# motordriverboard.net
KiCad netlist of a schematic drawn in EAGLE
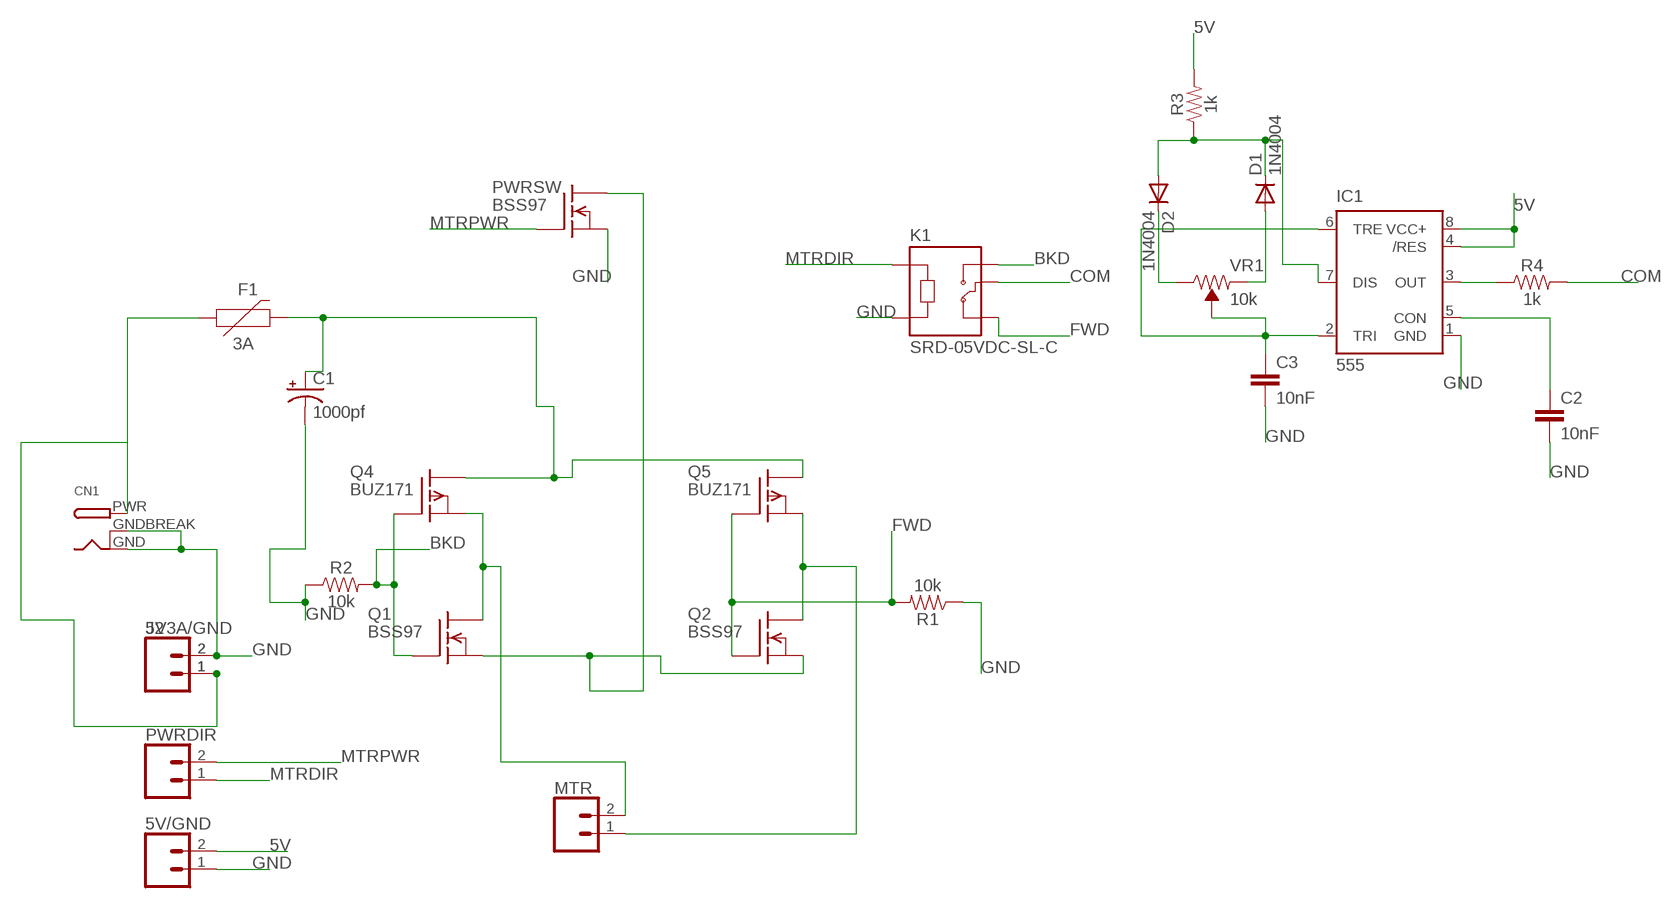
[diagram p0: schematic, sheet 1]

(export (version "E")
  (design (tool "Eeschema 10.0.6"))
  (components
    (comp (ref "5V/GND")
      (value "CONN_023.5MM")
      (footprint "eagle-import:SCREWTERMINAL-3.5MM-2")
      (libsource (lib "eagle-import") (part "CONN_023.5MM"))
    )
    (comp (ref "5V3A/GND")
      (value "CONN_023.5MM")
      (footprint "eagle-import:SCREWTERMINAL-3.5MM-2")
      (libsource (lib "eagle-import") (part "CONN_023.5MM"))
    )
    (comp (ref "C1")
      (value "1000pf")
      (footprint "eagle-import:E5-6")
      (libsource (lib "eagle-import") (part "CPOL-USE5-6"))
    )
    (comp (ref "C2")
      (value "10nF")
      (footprint "eagle-import:CAP-PTH-10MM")
      (libsource (lib "eagle-import") (part "10NF-PTH-10MM-10000V-1-%"))
    )
    (comp (ref "C3")
      (value "10nF")
      (footprint "eagle-import:CAP-PTH-10MM")
      (libsource (lib "eagle-import") (part "10NF-PTH-10MM-10000V-1-%"))
    )
    (comp (ref "CN1")
      (value "DCBARRELPTH")
      (footprint "eagle-import:DCJACK_2MM_PTH")
      (libsource (lib "eagle-import") (part "DCBARRELPTH"))
    )
    (comp (ref "D1")
      (value "1N4004")
      (footprint "eagle-import:DO41-10")
      (libsource (lib "eagle-import") (part "1N4004"))
    )
    (comp (ref "D2")
      (value "1N4004")
      (footprint "eagle-import:DO41-10")
      (libsource (lib "eagle-import") (part "1N4004"))
    )
    (comp (ref "F1")
      (value "3A")
      (footprint "eagle-import:PTH")
      (libsource (lib "eagle-import") (part "PPTC_PTH"))
    )
    (comp (ref "IC1")
      (value "555")
      (footprint "eagle-import:DIP08")
      (libsource (lib "eagle-import") (part "555P"))
    )
    (comp (ref "J2")
      (value "CONN_023.5MM")
      (footprint "eagle-import:SCREWTERMINAL-3.5MM-2")
      (libsource (lib "eagle-import") (part "CONN_023.5MM"))
    )
    (comp (ref "K1")
      (value "SRD-05VDC-SL-C")
      (footprint "eagle-import:RELAY_SRD-05VDC-SL-C")
      (fields (field (name "MF") "Songle Relay"))
      (libsource (lib "eagle-import") (part "SRD-05VDC-SL-C"))
    )
    (comp (ref "MTR")
      (value "CONN_023.5MM")
      (footprint "eagle-import:SCREWTERMINAL-3.5MM-2")
      (libsource (lib "eagle-import") (part "CONN_023.5MM"))
    )
    (comp (ref "PWRDIR")
      (value "CONN_023.5MM")
      (footprint "eagle-import:SCREWTERMINAL-3.5MM-2")
      (libsource (lib "eagle-import") (part "CONN_023.5MM"))
    )
    (comp (ref "PWRSW")
      (value "BSS97")
      (footprint "eagle-import:TO202")
      (libsource (lib "eagle-import") (part "BSS97"))
    )
    (comp (ref "Q1")
      (value "BSS97")
      (footprint "eagle-import:TO202")
      (libsource (lib "eagle-import") (part "BSS97"))
    )
    (comp (ref "Q2")
      (value "BSS97")
      (footprint "eagle-import:TO202")
      (libsource (lib "eagle-import") (part "BSS97"))
    )
    (comp (ref "Q4")
      (value "BUZ171")
      (footprint "eagle-import:TO220")
      (libsource (lib "eagle-import") (part "BUZ171"))
    )
    (comp (ref "Q5")
      (value "BUZ171")
      (footprint "eagle-import:TO220")
      (libsource (lib "eagle-import") (part "BUZ171"))
    )
    (comp (ref "R1")
      (value "10k")
      (footprint "eagle-import:AXIAL-0.3")
      (libsource (lib "eagle-import") (part "15KOHM-HORIZ-1/4W-5%"))
    )
    (comp (ref "R2")
      (value "10k")
      (footprint "eagle-import:AXIAL-0.3")
      (libsource (lib "eagle-import") (part "15KOHM-HORIZ-1/4W-5%"))
    )
    (comp (ref "R3")
      (value "1k")
      (footprint "eagle-import:AXIAL-0.3")
      (libsource (lib "eagle-import") (part "1KOHM-HORIZ-1/4W-1%"))
    )
    (comp (ref "R4")
      (value "1k")
      (footprint "eagle-import:AXIAL-0.3")
      (libsource (lib "eagle-import") (part "1KOHM-HORIZ-1/4W-1%"))
    )
    (comp (ref "VR1")
      (value "10k")
      (footprint "eagle-import:TRIMPOT-PTH-3386U")
      (libsource (lib "eagle-import") (part "TRIMPOT-PTH-10MM-KNOB-1/2W-10%"))
    )
  )
  (nets
    (net (code "1") (name "/5V") (class "Default")
      (node (ref "5V/GND") (pin "2") (pinfunction "2_2") (pintype "passive"))
      (node (ref "IC1") (pin "4") (pinfunction "/RES_4") (pintype "input"))
      (node (ref "IC1") (pin "8") (pinfunction "VCC+_8") (pintype "power_in"))
      (node (ref "R3") (pin "P$2") (pinfunction "2_P$2") (pintype "passive"))
    )
    (net (code "2") (name "/BKD") (class "Default")
      (node (ref "K1") (pin "NO") (pinfunction "NO_NO") (pintype "passive"))
      (node (ref "Q1") (pin "3") (pinfunction "G_3") (pintype "passive"))
      (node (ref "Q4") (pin "1") (pinfunction "G_1") (pintype "passive"))
      (node (ref "R2") (pin "P$2") (pinfunction "2_P$2") (pintype "passive"))
    )
    (net (code "3") (name "/COM") (class "Default")
      (node (ref "K1") (pin "COM") (pinfunction "COM_COM") (pintype "passive"))
      (node (ref "R4") (pin "P$2") (pinfunction "2_P$2") (pintype "passive"))
    )
    (net (code "4") (name "/FWD") (class "Default")
      (node (ref "K1") (pin "NC") (pinfunction "NC_NC") (pintype "passive"))
      (node (ref "Q2") (pin "3") (pinfunction "G_3") (pintype "passive"))
      (node (ref "Q5") (pin "1") (pinfunction "G_1") (pintype "passive"))
      (node (ref "R1") (pin "P$2") (pinfunction "2_P$2") (pintype "passive"))
    )
    (net (code "5") (name "/GND") (class "Default")
      (node (ref "5V/GND") (pin "1") (pinfunction "1_1") (pintype "passive"))
      (node (ref "5V3A/GND") (pin "2") (pinfunction "2_2") (pintype "passive"))
      (node (ref "C1") (pin "-") (pinfunction "-_-") (pintype "passive"))
      (node (ref "C2") (pin "2") (pinfunction "2_2") (pintype "passive"))
      (node (ref "C3") (pin "2") (pinfunction "2_2") (pintype "passive"))
      (node (ref "CN1") (pin "GND") (pinfunction "GND_GND") (pintype "power_in"))
      (node (ref "CN1") (pin "GNDBREAK") (pinfunction "GNDBREAK_GNDBREAK") (pintype "power_in"))
      (node (ref "IC1") (pin "1") (pinfunction "GND_1") (pintype "power_in"))
      (node (ref "J2") (pin "2") (pinfunction "2_2") (pintype "passive"))
      (node (ref "K1") (pin "A2") (pinfunction "A2_A2") (pintype "passive"))
      (node (ref "PWRSW") (pin "1") (pinfunction "S_1") (pintype "passive"))
      (node (ref "R1") (pin "P$1") (pinfunction "1_P$1") (pintype "passive"))
      (node (ref "R2") (pin "P$1") (pinfunction "1_P$1") (pintype "passive"))
    )
    (net (code "6") (name "/MTRDIR") (class "Default")
      (node (ref "K1") (pin "A1") (pinfunction "A1_A1") (pintype "passive"))
      (node (ref "PWRDIR") (pin "1") (pinfunction "1_1") (pintype "passive"))
    )
    (net (code "7") (name "/MTRPWR") (class "Default")
      (node (ref "PWRDIR") (pin "2") (pinfunction "2_2") (pintype "passive"))
      (node (ref "PWRSW") (pin "3") (pinfunction "G_3") (pintype "passive"))
    )
    (net (code "8") (name "Net-(F1-1)") (class "Default")
      (node (ref "5V3A/GND") (pin "1") (pinfunction "1_1") (pintype "passive"))
      (node (ref "CN1") (pin "PWR") (pinfunction "PWR_PWR") (pintype "power_in"))
      (node (ref "F1") (pin "P$1") (pinfunction "1_P$1") (pintype "bidirectional"))
      (node (ref "J2") (pin "1") (pinfunction "1_1") (pintype "passive"))
    )
    (net (code "9") (name "Net-(F1-2)") (class "Default")
      (node (ref "C1") (pin "+") (pinfunction "+_+") (pintype "passive"))
      (node (ref "F1") (pin "P$2") (pinfunction "2_P$2") (pintype "bidirectional"))
      (node (ref "Q4") (pin "2") (pinfunction "D_2") (pintype "passive"))
      (node (ref "Q5") (pin "2") (pinfunction "D_2") (pintype "passive"))
    )
    (net (code "10") (name "Net-(IC1-CON)") (class "Default")
      (node (ref "C2") (pin "1") (pinfunction "1_1") (pintype "passive"))
      (node (ref "IC1") (pin "5") (pinfunction "CON_5") (pintype "input"))
    )
    (net (code "11") (name "Net-(IC1-DIS)") (class "Default")
      (node (ref "D1") (pin "C") (pinfunction "C_C") (pintype "passive"))
      (node (ref "D2") (pin "A") (pinfunction "A_A") (pintype "passive"))
      (node (ref "IC1") (pin "7") (pinfunction "DIS_7") (pintype "input"))
      (node (ref "R3") (pin "P$1") (pinfunction "1_P$1") (pintype "passive"))
    )
    (net (code "12") (name "Net-(IC1-OUT)") (class "Default")
      (node (ref "IC1") (pin "3") (pinfunction "OUT_3") (pintype "output"))
      (node (ref "R4") (pin "P$1") (pinfunction "1_P$1") (pintype "passive"))
    )
    (net (code "13") (name "Net-(IC1-TRE)") (class "Default")
      (node (ref "C3") (pin "1") (pinfunction "1_1") (pintype "passive"))
      (node (ref "IC1") (pin "2") (pinfunction "TRI_2") (pintype "input"))
      (node (ref "IC1") (pin "6") (pinfunction "TRE_6") (pintype "input"))
      (node (ref "VR1") (pin "2") (pinfunction "WIPER_2") (pintype "passive"))
    )
    (net (code "14") (name "Net-(PWRSW-D)") (class "Default")
      (node (ref "PWRSW") (pin "2") (pinfunction "D_2") (pintype "passive"))
      (node (ref "Q1") (pin "1") (pinfunction "S_1") (pintype "passive"))
      (node (ref "Q2") (pin "1") (pinfunction "S_1") (pintype "passive"))
    )
    (net (code "15") (name "Net-(Q1-D)") (class "Default")
      (node (ref "MTR") (pin "2") (pinfunction "2_2") (pintype "passive"))
      (node (ref "Q1") (pin "2") (pinfunction "D_2") (pintype "passive"))
      (node (ref "Q4") (pin "3") (pinfunction "S_3") (pintype "passive"))
    )
    (net (code "16") (name "Net-(Q2-D)") (class "Default")
      (node (ref "MTR") (pin "1") (pinfunction "1_1") (pintype "passive"))
      (node (ref "Q2") (pin "2") (pinfunction "D_2") (pintype "passive"))
      (node (ref "Q5") (pin "3") (pinfunction "S_3") (pintype "passive"))
    )
    (net (code "17") (name "Net-(VR1-CCW)") (class "Default")
      (node (ref "D1") (pin "A") (pinfunction "A_A") (pintype "passive"))
      (node (ref "VR1") (pin "1") (pinfunction "CCW_1") (pintype "passive"))
    )
    (net (code "18") (name "Net-(VR1-CW)") (class "Default")
      (node (ref "D2") (pin "C") (pinfunction "C_C") (pintype "passive"))
      (node (ref "VR1") (pin "3") (pinfunction "CW_3") (pintype "passive"))
    )
  )
)
